# Thermostat.net
KiCad netlist of a schematic drawn in EAGLE
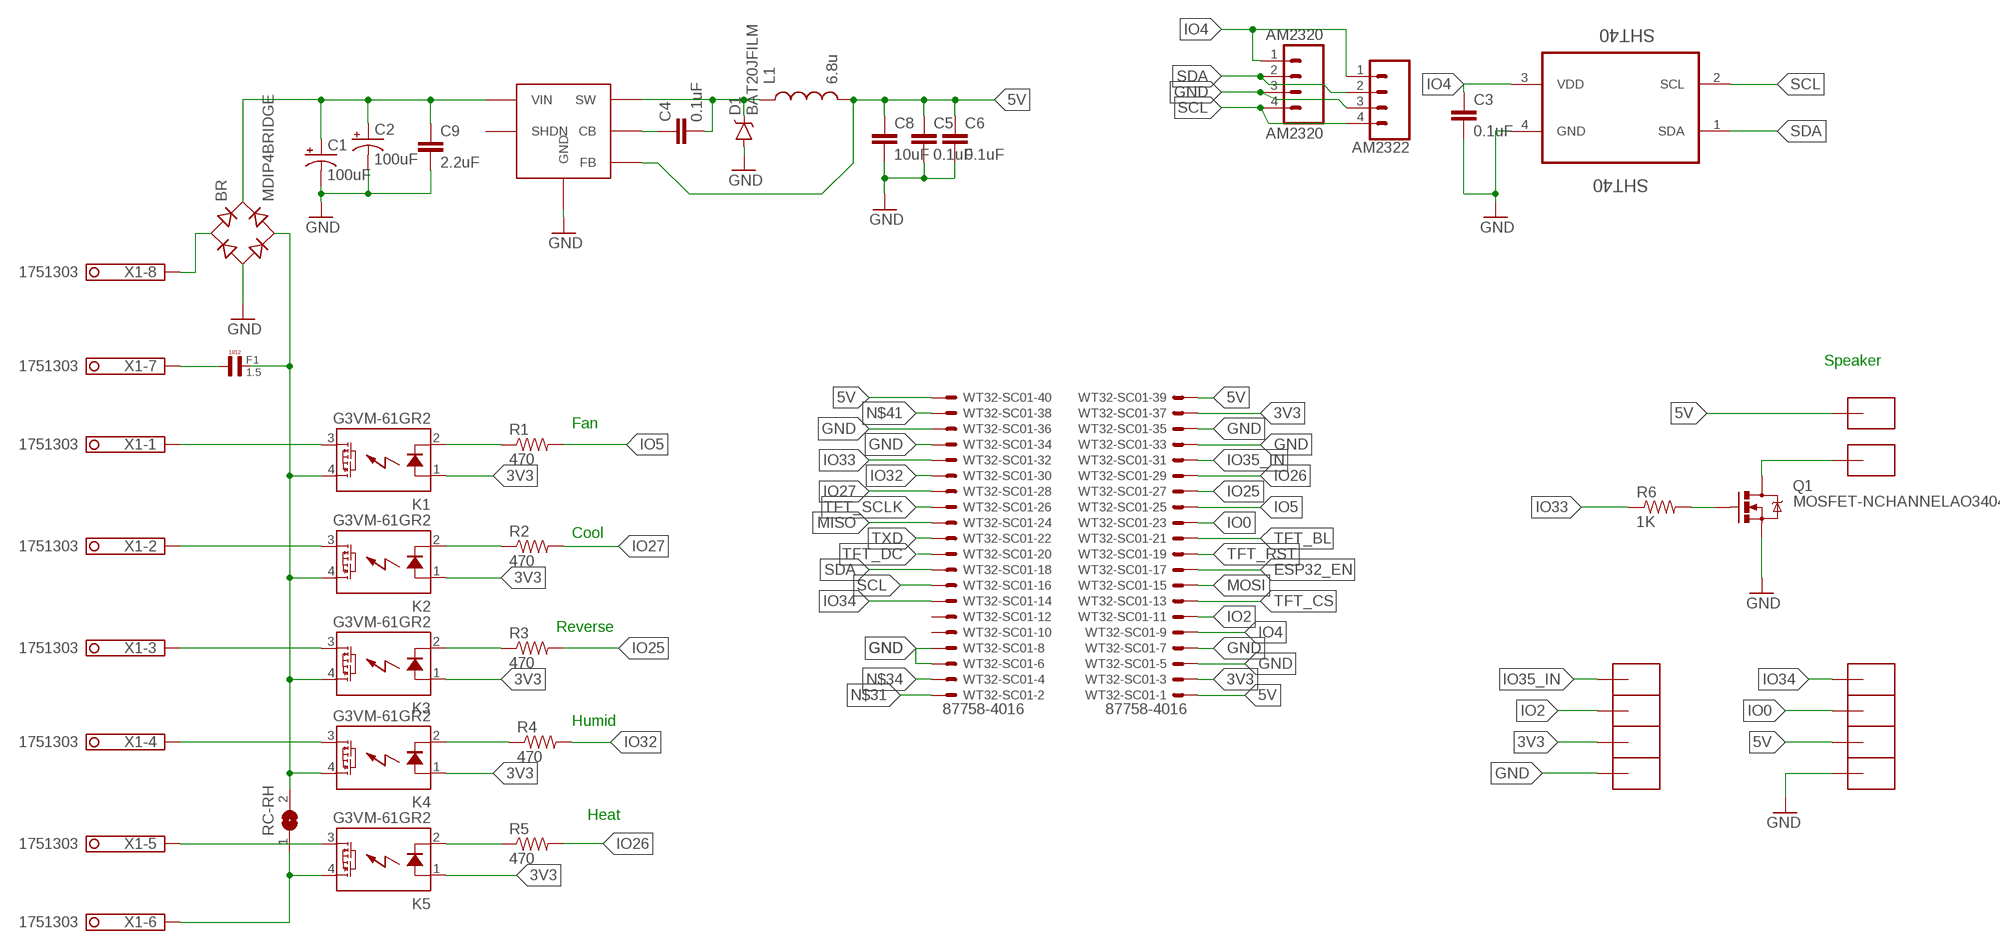
[diagram p0: schematic, sheet 1]

(export (version "E")
  (design (tool "Eeschema 10.0.6"))
  (components
    (comp (ref "AM2320")
      (value "AM2320")
      (footprint "eagle-import:1X04")
      (libsource (lib "eagle-import") (part "M04PTH"))
    )
    (comp (ref "AM2322")
      (value "CONN_041.27MM")
      (footprint "eagle-import:1X04_1.27MM")
      (libsource (lib "eagle-import") (part "CONN_041.27MM"))
    )
    (comp (ref "BR")
      (value "MDIP4BRIDGE")
      (footprint "eagle-import:MICRODIP4")
      (libsource (lib "eagle-import") (part "MDIP4BRIDGE"))
    )
    (comp (ref "C1")
      (value "100uF")
      (footprint "eagle-import:PANASONIC_C")
      (libsource (lib "eagle-import") (part "CAP_POLC"))
    )
    (comp (ref "C2")
      (value "100uF")
      (footprint "eagle-import:PANASONIC_C")
      (libsource (lib "eagle-import") (part "CAP_POLC"))
    )
    (comp (ref "C3")
      (value "0.1uF")
      (footprint "eagle-import:0805")
      (libsource (lib "eagle-import") (part "CAP0805"))
    )
    (comp (ref "C4")
      (value "0.1uF")
      (footprint "eagle-import:0805")
      (libsource (lib "eagle-import") (part "CAP0805"))
    )
    (comp (ref "C5")
      (value "0.1uF")
      (footprint "eagle-import:0805")
      (libsource (lib "eagle-import") (part "CAP0805"))
    )
    (comp (ref "C6")
      (value "0.1uF")
      (footprint "eagle-import:0805")
      (libsource (lib "eagle-import") (part "CAP0805"))
    )
    (comp (ref "C8")
      (value "10uF")
      (footprint "eagle-import:0805")
      (libsource (lib "eagle-import") (part "CAP0805"))
    )
    (comp (ref "C9")
      (value "2.2uF")
      (footprint "eagle-import:0805")
      (libsource (lib "eagle-import") (part "CAP0805"))
    )
    (comp (ref "D1")
      (value "BAT20JFILM")
      (footprint "eagle-import:SOD-323")
      (libsource (lib "eagle-import") (part "BAT20JFILM"))
    )
    (comp (ref "F1")
      (value "1.5")
      (footprint "eagle-import:L4,8")
      (libsource (lib "eagle-import") (part "0,1µF"))
    )
    (comp (ref "K1")
      (value "G3VM-61GR2")
      (footprint "eagle-import:SOP04")
      (libsource (lib "eagle-import") (part "AQYSOP22"))
    )
    (comp (ref "K2")
      (value "G3VM-61GR2")
      (footprint "eagle-import:SOP04")
      (libsource (lib "eagle-import") (part "AQYSOP22"))
    )
    (comp (ref "K3")
      (value "G3VM-61GR2")
      (footprint "eagle-import:SOP04")
      (libsource (lib "eagle-import") (part "AQYSOP22"))
    )
    (comp (ref "K4")
      (value "G3VM-61GR2")
      (footprint "eagle-import:SOP04")
      (libsource (lib "eagle-import") (part "AQYSOP22"))
    )
    (comp (ref "K5")
      (value "G3VM-61GR2")
      (footprint "eagle-import:SOP04")
      (libsource (lib "eagle-import") (part "AQYSOP22"))
    )
    (comp (ref "L1")
      (value "6.8u")
      (footprint "eagle-import:1007")
      (libsource (lib "eagle-import") (part "INDUCTOR1007"))
    )
    (comp (ref "Q1")
      (value "MOSFET-NCHANNELAO3404A")
      (footprint "eagle-import:SOT23-3")
      (libsource (lib "eagle-import") (part "MOSFET-NCHANNELAO3404A"))
    )
    (comp (ref "R1")
      (value "470")
      (footprint "eagle-import:0805")
      (libsource (lib "eagle-import") (part "RESISTOR0805-RES"))
    )
    (comp (ref "R2")
      (value "470")
      (footprint "eagle-import:0805")
      (libsource (lib "eagle-import") (part "RESISTOR0805-RES"))
    )
    (comp (ref "R3")
      (value "470")
      (footprint "eagle-import:0805")
      (libsource (lib "eagle-import") (part "RESISTOR0805-RES"))
    )
    (comp (ref "R4")
      (value "470")
      (footprint "eagle-import:0805")
      (libsource (lib "eagle-import") (part "RESISTOR0805-RES"))
    )
    (comp (ref "R5")
      (value "470")
      (footprint "eagle-import:0805")
      (libsource (lib "eagle-import") (part "RESISTOR0805-RES"))
    )
    (comp (ref "R6")
      (value "1K")
      (footprint "eagle-import:0805")
      (libsource (lib "eagle-import") (part "SparkFun-Resistors_RESISTOR0805-RES"))
    )
    (comp (ref "RC-RH")
      (value "SJ")
      (footprint "eagle-import:SJ")
      (libsource (lib "eagle-import") (part "SJ"))
    )
    (comp (ref "SHT40")
      (value "SHT40")
      (footprint "eagle-import:SHT40")
      (libsource (lib "eagle-import") (part "SHT40"))
    )
    (comp (ref "U$1")
      (value "SMD-PAD1SMD-PAD80X32")
      (footprint "eagle-import:SMD-PAD6")
      (libsource (lib "eagle-import") (part "SMD-PAD1SMD-PAD80X32"))
    )
    (comp (ref "U$2")
      (value "SMD-PAD1SMD-PAD80X32")
      (footprint "eagle-import:SMD-PAD6")
      (libsource (lib "eagle-import") (part "SMD-PAD1SMD-PAD80X32"))
    )
    (comp (ref "U$3")
      (value "SMD-PAD1SMD-PAD80X32")
      (footprint "eagle-import:SMD-PAD6")
      (libsource (lib "eagle-import") (part "SMD-PAD1SMD-PAD80X32"))
    )
    (comp (ref "U$4")
      (value "SMD-PAD1SMD-PAD80X32")
      (footprint "eagle-import:SMD-PAD6")
      (libsource (lib "eagle-import") (part "SMD-PAD1SMD-PAD80X32"))
    )
    (comp (ref "U$5")
      (value "SMD-PAD1SMD-PAD80X32")
      (footprint "eagle-import:SMD-PAD6")
      (libsource (lib "eagle-import") (part "SMD-PAD1SMD-PAD80X32"))
    )
    (comp (ref "U$6")
      (value "SMD-PAD1SMD-PAD80X32")
      (footprint "eagle-import:SMD-PAD6")
      (libsource (lib "eagle-import") (part "SMD-PAD1SMD-PAD80X32"))
    )
    (comp (ref "U$7")
      (value "SMD-PAD1SMD-PAD80X32")
      (footprint "eagle-import:SMD-PAD6")
      (libsource (lib "eagle-import") (part "SMD-PAD1SMD-PAD80X32"))
    )
    (comp (ref "U$9")
      (value "SMD-PAD1SMD-PAD80X32")
      (footprint "eagle-import:SMD-PAD6")
      (libsource (lib "eagle-import") (part "SMD-PAD1SMD-PAD80X32"))
    )
    (comp (ref "U$10")
      (value "SMD-PAD1SMD-PAD80X32")
      (footprint "eagle-import:SMD-PAD6")
      (libsource (lib "eagle-import") (part "SMD-PAD1SMD-PAD80X32"))
    )
    (comp (ref "U$11")
      (value "SMD-PAD1SMD-PAD80X32")
      (footprint "eagle-import:SMD-PAD6")
      (libsource (lib "eagle-import") (part "SMD-PAD1SMD-PAD80X32"))
    )
    (comp (ref "VREG")
      (value "LMR16006YQ")
      (footprint "eagle-import:SOT-23-6")
      (libsource (lib "eagle-import") (part "LMR16006YQ"))
    )
    (comp (ref "WT32-SC01")
      (value "87758-4016")
      (footprint "eagle-import:87758-4016")
      (fields (field (name "MF") "MOLEX"))
      (libsource (lib "eagle-import") (part "87758-4016"))
    )
    (comp (ref "X1")
      (value "1751303")
      (footprint "eagle-import:1751303")
      (libsource (lib "eagle-import") (part "1751303"))
    )
  )
  (nets
    (net (code "1") (name "3V3") (class "Default")
      (node (ref "K1") (pin "1") (pinfunction "A_1") (pintype "passive"))
      (node (ref "K2") (pin "1") (pinfunction "A_1") (pintype "passive"))
      (node (ref "K3") (pin "1") (pinfunction "A_1") (pintype "passive"))
      (node (ref "K4") (pin "1") (pinfunction "A_1") (pintype "passive"))
      (node (ref "K5") (pin "1") (pinfunction "A_1") (pintype "passive"))
      (node (ref "U$1") (pin ">PAD") (pinfunction "P$1_>PAD") (pintype "bidirectional"))
      (node (ref "WT32-SC01") (pin "3") (pinfunction "S_3") (pintype "passive"))
      (node (ref "WT32-SC01") (pin "37") (pinfunction "S_37") (pintype "passive"))
    )
    (net (code "2") (name "5V") (class "Default")
      (node (ref "C5") (pin "1") (pinfunction "1_1") (pintype "passive"))
      (node (ref "C6") (pin "1") (pinfunction "1_1") (pintype "passive"))
      (node (ref "C8") (pin "1") (pinfunction "1_1") (pintype "passive"))
      (node (ref "L1") (pin "2") (pinfunction "2_2") (pintype "passive"))
      (node (ref "U$5") (pin ">PAD") (pinfunction "P$1_>PAD") (pintype "bidirectional"))
      (node (ref "U$7") (pin ">PAD") (pinfunction "P$1_>PAD") (pintype "bidirectional"))
      (node (ref "VREG") (pin "3") (pinfunction "FB_3") (pintype "input"))
      (node (ref "WT32-SC01") (pin "1") (pinfunction "S_1") (pintype "passive"))
      (node (ref "WT32-SC01") (pin "39") (pinfunction "S_39") (pintype "passive"))
      (node (ref "WT32-SC01") (pin "40") (pinfunction "S_40") (pintype "passive"))
    )
    (net (code "3") (name "ESP32_EN") (class "Default")
      (node (ref "WT32-SC01") (pin "17") (pinfunction "S_17") (pintype "passive"))
    )
    (net (code "4") (name "GND") (class "Default")
      (node (ref "AM2320") (pin "3") (pinfunction "3_3") (pintype "passive"))
      (node (ref "AM2322") (pin "3") (pinfunction "3_3") (pintype "passive"))
      (node (ref "BR") (pin "-") (pinfunction "-_-") (pintype "passive"))
      (node (ref "C1") (pin "-") (pinfunction "-_-") (pintype "passive"))
      (node (ref "C2") (pin "-") (pinfunction "-_-") (pintype "passive"))
      (node (ref "C3") (pin "2") (pinfunction "2_2") (pintype "passive"))
      (node (ref "C5") (pin "2") (pinfunction "2_2") (pintype "passive"))
      (node (ref "C6") (pin "2") (pinfunction "2_2") (pintype "passive"))
      (node (ref "C8") (pin "2") (pinfunction "2_2") (pintype "passive"))
      (node (ref "C9") (pin "2") (pinfunction "2_2") (pintype "passive"))
      (node (ref "D1") (pin "A") (pinfunction "A_A") (pintype "passive"))
      (node (ref "Q1") (pin "2") (pinfunction "S_2") (pintype "passive"))
      (node (ref "SHT40") (pin "4") (pinfunction "GND_4") (pintype "bidirectional"))
      (node (ref "U$2") (pin ">PAD") (pinfunction "P$1_>PAD") (pintype "bidirectional"))
      (node (ref "U$9") (pin ">PAD") (pinfunction "P$1_>PAD") (pintype "bidirectional"))
      (node (ref "VREG") (pin "2") (pinfunction "GND_2") (pintype "input"))
      (node (ref "WT32-SC01") (pin "33") (pinfunction "S_33") (pintype "passive"))
      (node (ref "WT32-SC01") (pin "34") (pinfunction "S_34") (pintype "passive"))
      (node (ref "WT32-SC01") (pin "35") (pinfunction "S_35") (pintype "passive"))
      (node (ref "WT32-SC01") (pin "36") (pinfunction "S_36") (pintype "passive"))
      (node (ref "WT32-SC01") (pin "5") (pinfunction "S_5") (pintype "passive"))
      (node (ref "WT32-SC01") (pin "6") (pinfunction "S_6") (pintype "passive"))
      (node (ref "WT32-SC01") (pin "7") (pinfunction "S_7") (pintype "passive"))
      (node (ref "WT32-SC01") (pin "8") (pinfunction "S_8") (pintype "passive"))
    )
    (net (code "5") (name "IO0") (class "Default")
      (node (ref "U$10") (pin ">PAD") (pinfunction "P$1_>PAD") (pintype "bidirectional"))
      (node (ref "WT32-SC01") (pin "23") (pinfunction "S_23") (pintype "passive"))
    )
    (net (code "6") (name "IO2") (class "Default")
      (node (ref "U$3") (pin ">PAD") (pinfunction "P$1_>PAD") (pintype "bidirectional"))
      (node (ref "WT32-SC01") (pin "11") (pinfunction "S_11") (pintype "passive"))
    )
    (net (code "7") (name "IO4") (class "Default")
      (node (ref "AM2320") (pin "1") (pinfunction "1_1") (pintype "passive"))
      (node (ref "AM2322") (pin "1") (pinfunction "1_1") (pintype "passive"))
      (node (ref "C3") (pin "1") (pinfunction "1_1") (pintype "passive"))
      (node (ref "SHT40") (pin "3") (pinfunction "VDD_3") (pintype "bidirectional"))
      (node (ref "WT32-SC01") (pin "9") (pinfunction "S_9") (pintype "passive"))
    )
    (net (code "8") (name "IO5") (class "Default")
      (node (ref "R1") (pin "2") (pinfunction "2_2") (pintype "passive"))
      (node (ref "WT32-SC01") (pin "25") (pinfunction "S_25") (pintype "passive"))
    )
    (net (code "9") (name "IO25") (class "Default")
      (node (ref "R3") (pin "2") (pinfunction "2_2") (pintype "passive"))
      (node (ref "WT32-SC01") (pin "27") (pinfunction "S_27") (pintype "passive"))
    )
    (net (code "10") (name "IO26") (class "Default")
      (node (ref "R5") (pin "2") (pinfunction "2_2") (pintype "passive"))
      (node (ref "WT32-SC01") (pin "29") (pinfunction "S_29") (pintype "passive"))
    )
    (net (code "11") (name "IO27") (class "Default")
      (node (ref "R2") (pin "2") (pinfunction "2_2") (pintype "passive"))
      (node (ref "WT32-SC01") (pin "28") (pinfunction "S_28") (pintype "passive"))
    )
    (net (code "12") (name "IO32") (class "Default")
      (node (ref "R4") (pin "2") (pinfunction "2_2") (pintype "passive"))
      (node (ref "WT32-SC01") (pin "30") (pinfunction "S_30") (pintype "passive"))
    )
    (net (code "13") (name "IO33") (class "Default")
      (node (ref "R6") (pin "1") (pinfunction "1_1") (pintype "passive"))
      (node (ref "WT32-SC01") (pin "32") (pinfunction "S_32") (pintype "passive"))
    )
    (net (code "14") (name "IO34") (class "Default")
      (node (ref "U$6") (pin ">PAD") (pinfunction "P$1_>PAD") (pintype "bidirectional"))
      (node (ref "WT32-SC01") (pin "14") (pinfunction "S_14") (pintype "passive"))
    )
    (net (code "15") (name "IO35_IN") (class "Default")
      (node (ref "U$4") (pin ">PAD") (pinfunction "P$1_>PAD") (pintype "bidirectional"))
      (node (ref "WT32-SC01") (pin "31") (pinfunction "S_31") (pintype "passive"))
    )
    (net (code "16") (name "MISO") (class "Default")
      (node (ref "WT32-SC01") (pin "24") (pinfunction "S_24") (pintype "passive"))
    )
    (net (code "17") (name "MOSI") (class "Default")
      (node (ref "WT32-SC01") (pin "15") (pinfunction "S_15") (pintype "passive"))
    )
    (net (code "18") (name "N$31") (class "Default")
      (node (ref "WT32-SC01") (pin "2") (pinfunction "S_2") (pintype "passive"))
    )
    (net (code "19") (name "N$34") (class "Default")
      (node (ref "WT32-SC01") (pin "4") (pinfunction "S_4") (pintype "passive"))
    )
    (net (code "20") (name "N$41") (class "Default")
      (node (ref "WT32-SC01") (pin "38") (pinfunction "S_38") (pintype "passive"))
    )
    (net (code "21") (name "Net-(F1-1)") (class "Default")
      (node (ref "F1") (pin "P$1") (pinfunction "1_P$1") (pintype "passive"))
      (node (ref "X1") (pin "7") (pinfunction "K_7") (pintype "passive"))
    )
    (net (code "22") (name "Net-(F1-2)") (class "Default")
      (node (ref "BR") (pin "AC2") (pinfunction "AC2_AC2") (pintype "passive"))
      (node (ref "F1") (pin "P$2") (pinfunction "2_P$2") (pintype "passive"))
      (node (ref "K1") (pin "4") (pinfunction "DS1_4") (pintype "passive"))
      (node (ref "K2") (pin "4") (pinfunction "DS1_4") (pintype "passive"))
      (node (ref "K3") (pin "4") (pinfunction "DS1_4") (pintype "passive"))
      (node (ref "K4") (pin "4") (pinfunction "DS1_4") (pintype "passive"))
      (node (ref "RC-RH") (pin "2") (pinfunction "2_2") (pintype "passive"))
    )
    (net (code "23") (name "Net-(K1-DS2)") (class "Default")
      (node (ref "K1") (pin "3") (pinfunction "DS2_3") (pintype "passive"))
      (node (ref "X1") (pin "1") (pinfunction "K_1") (pintype "passive"))
    )
    (net (code "24") (name "Net-(K1-K)") (class "Default")
      (node (ref "K1") (pin "2") (pinfunction "K_2") (pintype "passive"))
      (node (ref "R1") (pin "1") (pinfunction "1_1") (pintype "passive"))
    )
    (net (code "25") (name "Net-(K2-DS2)") (class "Default")
      (node (ref "K2") (pin "3") (pinfunction "DS2_3") (pintype "passive"))
      (node (ref "X1") (pin "2") (pinfunction "K_2") (pintype "passive"))
    )
    (net (code "26") (name "Net-(K2-K)") (class "Default")
      (node (ref "K2") (pin "2") (pinfunction "K_2") (pintype "passive"))
      (node (ref "R2") (pin "1") (pinfunction "1_1") (pintype "passive"))
    )
    (net (code "27") (name "Net-(K3-DS2)") (class "Default")
      (node (ref "K3") (pin "3") (pinfunction "DS2_3") (pintype "passive"))
      (node (ref "X1") (pin "3") (pinfunction "K_3") (pintype "passive"))
    )
    (net (code "28") (name "Net-(K3-K)") (class "Default")
      (node (ref "K3") (pin "2") (pinfunction "K_2") (pintype "passive"))
      (node (ref "R3") (pin "1") (pinfunction "1_1") (pintype "passive"))
    )
    (net (code "29") (name "Net-(K4-DS2)") (class "Default")
      (node (ref "K4") (pin "3") (pinfunction "DS2_3") (pintype "passive"))
      (node (ref "X1") (pin "4") (pinfunction "K_4") (pintype "passive"))
    )
    (net (code "30") (name "Net-(K4-K)") (class "Default")
      (node (ref "K4") (pin "2") (pinfunction "K_2") (pintype "passive"))
      (node (ref "R4") (pin "1") (pinfunction "1_1") (pintype "passive"))
    )
    (net (code "31") (name "Net-(K5-DS1)") (class "Default")
      (node (ref "K5") (pin "4") (pinfunction "DS1_4") (pintype "passive"))
      (node (ref "RC-RH") (pin "1") (pinfunction "1_1") (pintype "passive"))
      (node (ref "X1") (pin "6") (pinfunction "K_6") (pintype "passive"))
    )
    (net (code "32") (name "Net-(K5-DS2)") (class "Default")
      (node (ref "K5") (pin "3") (pinfunction "DS2_3") (pintype "passive"))
      (node (ref "X1") (pin "5") (pinfunction "K_5") (pintype "passive"))
    )
    (net (code "33") (name "Net-(K5-K)") (class "Default")
      (node (ref "K5") (pin "2") (pinfunction "K_2") (pintype "passive"))
      (node (ref "R5") (pin "1") (pinfunction "1_1") (pintype "passive"))
    )
    (net (code "34") (name "Net-(Q1-D)") (class "Default")
      (node (ref "Q1") (pin "3") (pinfunction "D_3") (pintype "passive"))
      (node (ref "U$11") (pin ">PAD") (pinfunction "P$1_>PAD") (pintype "bidirectional"))
    )
    (net (code "35") (name "Net-(Q1-G)") (class "Default")
      (node (ref "Q1") (pin "1") (pinfunction "G_1") (pintype "passive"))
      (node (ref "R6") (pin "2") (pinfunction "2_2") (pintype "passive"))
    )
    (net (code "36") (name "Net-(VREG-CB)") (class "Default")
      (node (ref "C4") (pin "1") (pinfunction "1_1") (pintype "passive"))
      (node (ref "VREG") (pin "1") (pinfunction "CB_1") (pintype "input"))
    )
    (net (code "37") (name "Net-(VREG-SW)") (class "Default")
      (node (ref "C4") (pin "2") (pinfunction "2_2") (pintype "passive"))
      (node (ref "D1") (pin "C") (pinfunction "C_C") (pintype "passive"))
      (node (ref "L1") (pin "1") (pinfunction "1_1") (pintype "passive"))
      (node (ref "VREG") (pin "6") (pinfunction "SW_6") (pintype "output"))
    )
    (net (code "38") (name "Net-(VREG-VIN)") (class "Default")
      (node (ref "BR") (pin "+") (pinfunction "+_+") (pintype "passive"))
      (node (ref "C1") (pin "+") (pinfunction "+_+") (pintype "passive"))
      (node (ref "C2") (pin "+") (pinfunction "+_+") (pintype "passive"))
      (node (ref "C9") (pin "1") (pinfunction "1_1") (pintype "passive"))
      (node (ref "VREG") (pin "5") (pinfunction "VIN_5") (pintype "input"))
    )
    (net (code "39") (name "Net-(X1H-K)") (class "Default")
      (node (ref "BR") (pin "AC1") (pinfunction "AC1_AC1") (pintype "passive"))
      (node (ref "X1") (pin "8") (pinfunction "K_8") (pintype "passive"))
    )
    (net (code "40") (name "SCL") (class "Default")
      (node (ref "AM2320") (pin "4") (pinfunction "4_4") (pintype "passive"))
      (node (ref "AM2322") (pin "4") (pinfunction "4_4") (pintype "passive"))
      (node (ref "SHT40") (pin "2") (pinfunction "SCL_2") (pintype "input"))
      (node (ref "WT32-SC01") (pin "16") (pinfunction "S_16") (pintype "passive"))
    )
    (net (code "41") (name "SDA") (class "Default")
      (node (ref "AM2320") (pin "2") (pinfunction "2_2") (pintype "passive"))
      (node (ref "AM2322") (pin "2") (pinfunction "2_2") (pintype "passive"))
      (node (ref "SHT40") (pin "1") (pinfunction "SDA_1") (pintype "power_in"))
      (node (ref "WT32-SC01") (pin "18") (pinfunction "S_18") (pintype "passive"))
    )
    (net (code "42") (name "TFT_BL") (class "Default")
      (node (ref "WT32-SC01") (pin "21") (pinfunction "S_21") (pintype "passive"))
    )
    (net (code "43") (name "TFT_CS") (class "Default")
      (node (ref "WT32-SC01") (pin "13") (pinfunction "S_13") (pintype "passive"))
    )
    (net (code "44") (name "TFT_DC") (class "Default")
      (node (ref "WT32-SC01") (pin "20") (pinfunction "S_20") (pintype "passive"))
    )
    (net (code "45") (name "TFT_RST") (class "Default")
      (node (ref "WT32-SC01") (pin "19") (pinfunction "S_19") (pintype "passive"))
    )
    (net (code "46") (name "TFT_SCLK") (class "Default")
      (node (ref "WT32-SC01") (pin "26") (pinfunction "S_26") (pintype "passive"))
    )
    (net (code "47") (name "TXD") (class "Default")
      (node (ref "WT32-SC01") (pin "22") (pinfunction "S_22") (pintype "passive"))
    )
    (net (code "48") (name "unconnected-(VREG-SHDN-Pad4)") (class "Default")
      (node (ref "VREG") (pin "4") (pinfunction "SHDN_4") (pintype "input"))
    )
    (net (code "49") (name "unconnected-(WT32-SC01B-S-Pad10)") (class "Default")
      (node (ref "WT32-SC01") (pin "10") (pinfunction "S_10") (pintype "passive"))
    )
    (net (code "50") (name "unconnected-(WT32-SC01D-S-Pad12)") (class "Default")
      (node (ref "WT32-SC01") (pin "12") (pinfunction "S_12") (pintype "passive"))
    )
  )
)
